# MoteinoR6USB.net
KiCad netlist of a schematic drawn in EAGLE
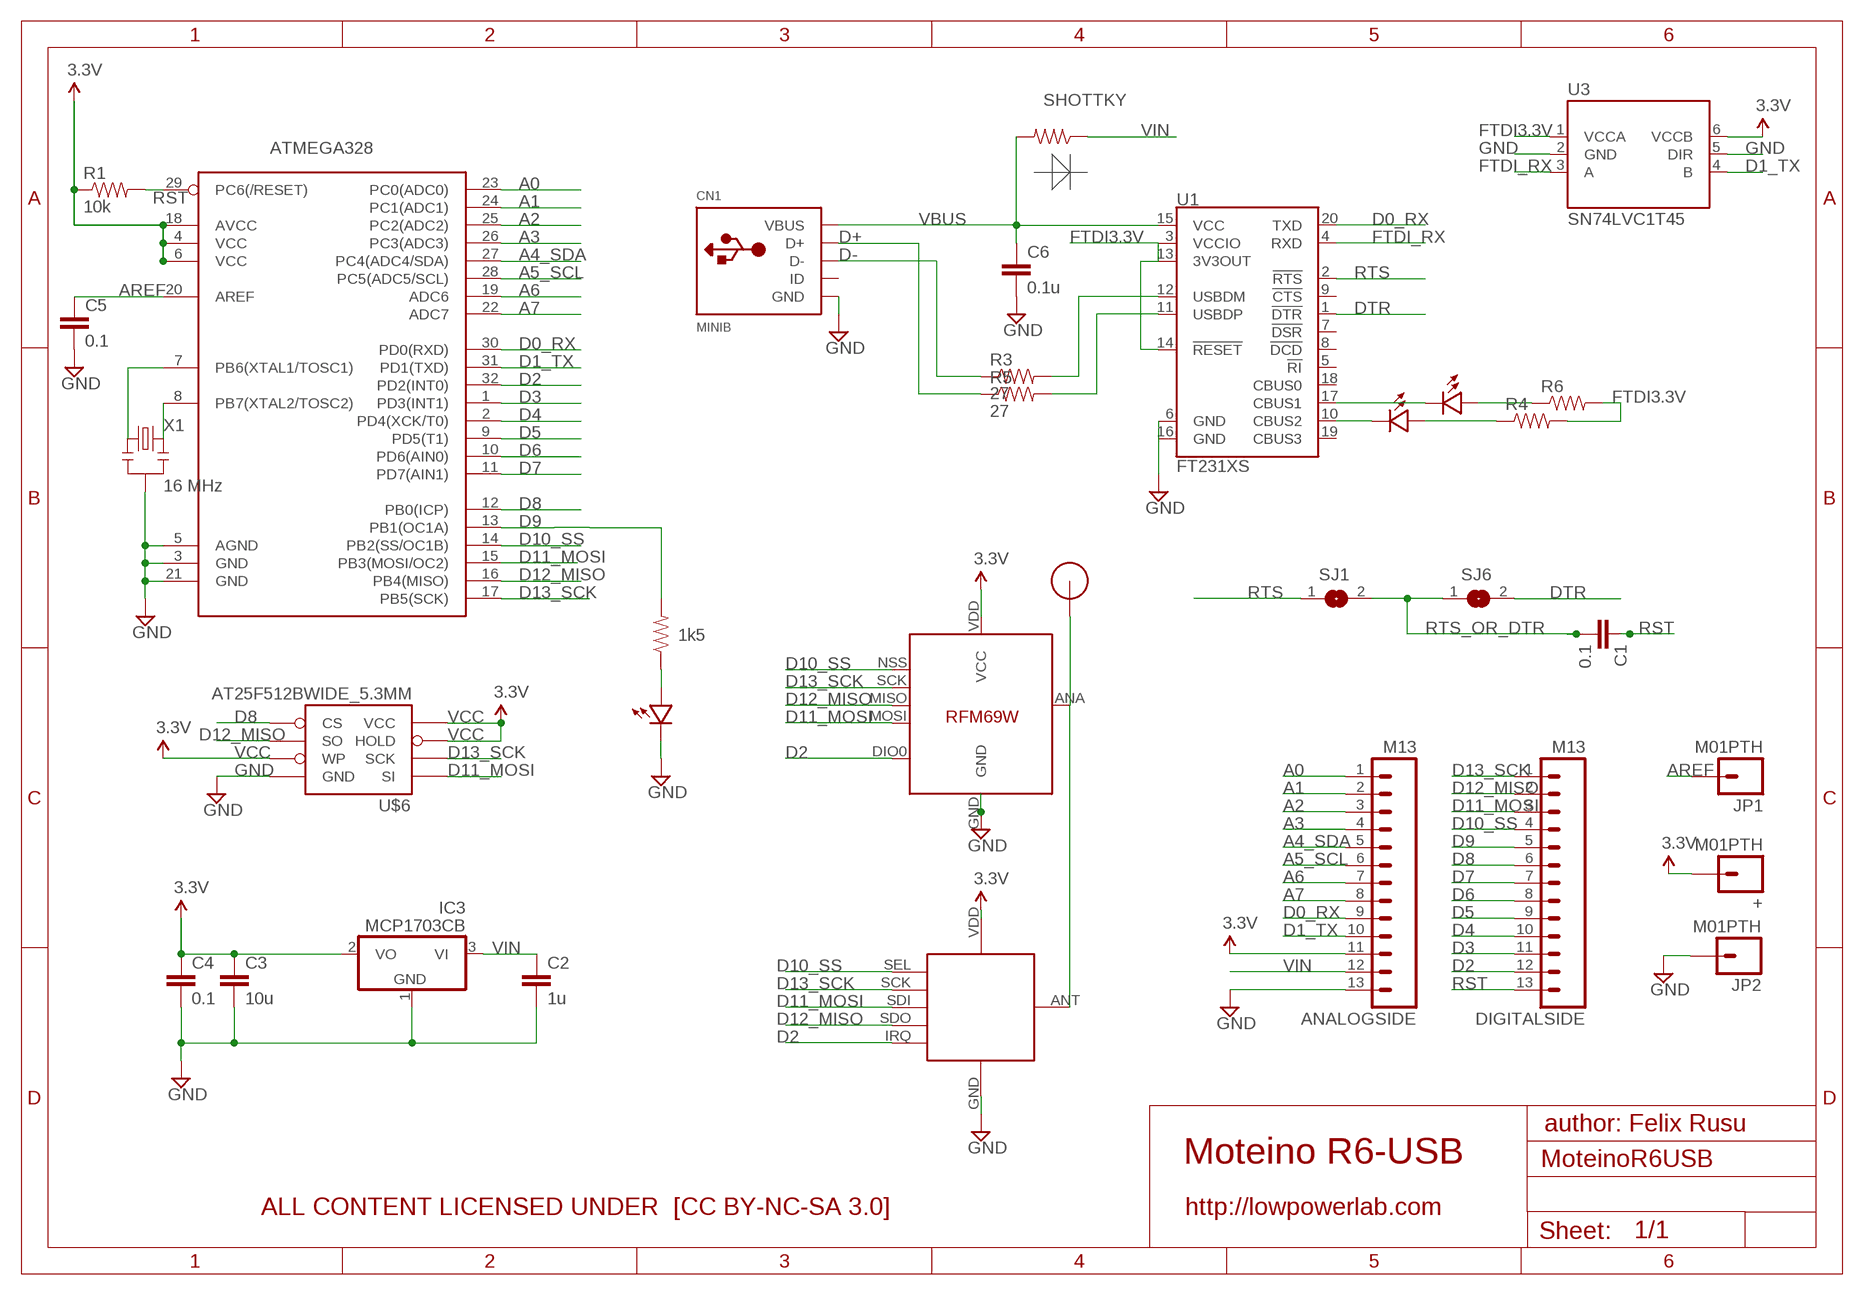
[diagram p0: schematic, sheet 1]

(export (version "E")
  (design (tool "Eeschema 10.0.6"))
  (components
    (comp (ref "+")
      (value "M01PTH")
      (footprint "eagle-import:1X01")
      (libsource (lib "eagle-import") (part "M01PTH"))
    )
    (comp (ref "ANALOGSIDE")
      (value "M13")
      (footprint "eagle-import:1X13")
      (libsource (lib "eagle-import") (part "M13"))
    )
    (comp (ref "ATMEGA328")
      (value "ATMega-328")
      (footprint "eagle-import:TQFP32-08")
      (libsource (lib "eagle-import") (part "ATMEGA168/328TQFP32"))
    )
    (comp (ref "C1")
      (value "0.1")
      (footprint "eagle-import:0603-CAP")
      (libsource (lib "eagle-import") (part "CAP0603-CAP"))
    )
    (comp (ref "C2")
      (value "1u")
      (footprint "eagle-import:0603-CAP")
      (libsource (lib "eagle-import") (part "CAP0603-CAP"))
    )
    (comp (ref "C3")
      (value "10u")
      (footprint "eagle-import:0805-CAP")
      (libsource (lib "eagle-import") (part "CAP0805-CAP"))
    )
    (comp (ref "C4")
      (value "0.1")
      (footprint "eagle-import:0603-CAP")
      (libsource (lib "eagle-import") (part "CAP0603-CAP"))
    )
    (comp (ref "C5")
      (value "0.1")
      (footprint "eagle-import:0603-CAP")
      (libsource (lib "eagle-import") (part "CAP0603-CAP"))
    )
    (comp (ref "C6")
      (value "0.1u")
      (footprint "eagle-import:0603-CAP")
      (libsource (lib "eagle-import") (part "CAP0603-CAP"))
    )
    (comp (ref "CN1")
      (value "MINIB")
      (footprint "eagle-import:USB-MINIB")
      (libsource (lib "eagle-import") (part "USBMINIB"))
    )
    (comp (ref "D")
      (value "SHOTTKY")
      (footprint "eagle-import:0603-RES")
      (libsource (lib "eagle-import") (part "RESISTOR0603-RES"))
    )
    (comp (ref "DIGITALSIDE")
      (value "M13")
      (footprint "eagle-import:1X13")
      (libsource (lib "eagle-import") (part "M13"))
    )
    (comp (ref "IC3")
      (value "MCP1703CB")
      (footprint "eagle-import:SOT23")
      (libsource (lib "eagle-import") (part "MCP1703CB"))
    )
    (comp (ref "JP1")
      (value "M01PTH")
      (footprint "eagle-import:1X01")
      (libsource (lib "eagle-import") (part "M01PTH"))
    )
    (comp (ref "JP2")
      (value "M01PTH")
      (footprint "eagle-import:1X01")
      (libsource (lib "eagle-import") (part "M01PTH"))
    )
    (comp (ref "R1")
      (value "10k")
      (footprint "eagle-import:0603-RES")
      (libsource (lib "eagle-import") (part "RESISTOR0603-RES"))
    )
    (comp (ref "R2")
      (value "1k5")
      (footprint "eagle-import:0603-RES")
      (libsource (lib "eagle-import") (part "RESISTOR0603-RES"))
    )
    (comp (ref "R3")
      (value "27")
      (footprint "eagle-import:0603-RES")
      (libsource (lib "eagle-import") (part "RESISTOR0603-RES"))
    )
    (comp (ref "R4")
      (value "RESISTOR0603-RES")
      (footprint "eagle-import:0603-RES")
      (libsource (lib "eagle-import") (part "RESISTOR0603-RES"))
    )
    (comp (ref "R5")
      (value "27")
      (footprint "eagle-import:0603-RES")
      (libsource (lib "eagle-import") (part "RESISTOR0603-RES"))
    )
    (comp (ref "R6")
      (value "RESISTOR0603-RES")
      (footprint "eagle-import:0603-RES")
      (libsource (lib "eagle-import") (part "RESISTOR0603-RES"))
    )
    (comp (ref "RFM12B")
      (value "RFM12B_MINPADS")
      (footprint "eagle-import:RFM12B-MINPADS")
      (libsource (lib "eagle-import") (part "RFM12B_MINPADS"))
    )
    (comp (ref "SJ1")
      (value "JUMPER")
      (footprint "eagle-import:SJW")
      (libsource (lib "eagle-import") (part "JUMPER"))
    )
    (comp (ref "SJ6")
      (value "JUMPER")
      (footprint "eagle-import:SJW")
      (libsource (lib "eagle-import") (part "JUMPER"))
    )
    (comp (ref "U$1")
      (value "RFM12B_ANTENNA")
      (footprint "eagle-import:RFM12B-ANTENNA")
      (libsource (lib "eagle-import") (part "RFM12B_ANTENNA"))
    )
    (comp (ref "U$2")
      (value "LED0603")
      (footprint "eagle-import:0603-LED")
      (libsource (lib "eagle-import") (part "LED0603"))
    )
    (comp (ref "U$4")
      (value "LED0603")
      (footprint "eagle-import:0603-LED")
      (libsource (lib "eagle-import") (part "LED0603"))
    )
    (comp (ref "U$5")
      (value "RFM69")
      (footprint "eagle-import:RFM69W-MINPADS")
      (libsource (lib "eagle-import") (part "RFM69"))
    )
    (comp (ref "U$6")
      (value "AT25F512BWIDE_5.3MM")
      (footprint "eagle-import:SO08WIDE")
      (libsource (lib "eagle-import") (part "AT25F512BWIDE_5.3MM"))
    )
    (comp (ref "U$7")
      (value "LED0603")
      (footprint "eagle-import:0603-LED")
      (libsource (lib "eagle-import") (part "LED0603"))
    )
    (comp (ref "U1")
      (value "FT231XS")
      (footprint "eagle-import:SSOP20_L")
      (libsource (lib "eagle-import") (part "FT231XS"))
    )
    (comp (ref "U3")
      (value "SN74LVC1T45")
      (footprint "eagle-import:SOT23-6")
      (libsource (lib "eagle-import") (part "SN74LVC1T45SOT-23"))
    )
    (comp (ref "X1")
      (value "16 MHz")
      (footprint "eagle-import:RESONATOR-SMD")
      (libsource (lib "eagle-import") (part "RESONATORSMD"))
    )
  )
  (nets
    (net (code "1") (name "/A0") (class "Default")
      (node (ref "ANALOGSIDE") (pin "1") (pinfunction "1_1") (pintype "passive"))
      (node (ref "ATMEGA328") (pin "23") (pinfunction "PC0(ADC0)_23") (pintype "bidirectional"))
    )
    (net (code "2") (name "/A1") (class "Default")
      (node (ref "ANALOGSIDE") (pin "2") (pinfunction "2_2") (pintype "passive"))
      (node (ref "ATMEGA328") (pin "24") (pinfunction "PC1(ADC1)_24") (pintype "bidirectional"))
    )
    (net (code "3") (name "/A2") (class "Default")
      (node (ref "ANALOGSIDE") (pin "3") (pinfunction "3_3") (pintype "passive"))
      (node (ref "ATMEGA328") (pin "25") (pinfunction "PC2(ADC2)_25") (pintype "bidirectional"))
    )
    (net (code "4") (name "/A3") (class "Default")
      (node (ref "ANALOGSIDE") (pin "4") (pinfunction "4_4") (pintype "passive"))
      (node (ref "ATMEGA328") (pin "26") (pinfunction "PC3(ADC3)_26") (pintype "bidirectional"))
    )
    (net (code "5") (name "/A4_SDA") (class "Default")
      (node (ref "ANALOGSIDE") (pin "5") (pinfunction "5_5") (pintype "passive"))
      (node (ref "ATMEGA328") (pin "27") (pinfunction "PC4(ADC4/SDA)_27") (pintype "bidirectional"))
    )
    (net (code "6") (name "/A5_SCL") (class "Default")
      (node (ref "ANALOGSIDE") (pin "6") (pinfunction "6_6") (pintype "passive"))
      (node (ref "ATMEGA328") (pin "28") (pinfunction "PC5(ADC5/SCL)_28") (pintype "bidirectional"))
    )
    (net (code "7") (name "/A6") (class "Default")
      (node (ref "ANALOGSIDE") (pin "7") (pinfunction "7_7") (pintype "passive"))
      (node (ref "ATMEGA328") (pin "19") (pinfunction "ADC6_19") (pintype "bidirectional"))
    )
    (net (code "8") (name "/A7") (class "Default")
      (node (ref "ANALOGSIDE") (pin "8") (pinfunction "8_8") (pintype "passive"))
      (node (ref "ATMEGA328") (pin "22") (pinfunction "ADC7_22") (pintype "bidirectional"))
    )
    (net (code "9") (name "/AREF") (class "Default")
      (node (ref "ATMEGA328") (pin "20") (pinfunction "AREF_20") (pintype "bidirectional"))
      (node (ref "C5") (pin "1") (pinfunction "1_1") (pintype "passive"))
      (node (ref "JP1") (pin "1") (pinfunction "1_1") (pintype "passive"))
    )
    (net (code "10") (name "/D+") (class "Default")
      (node (ref "CN1") (pin "D+") (pinfunction "D+_D+") (pintype "bidirectional"))
      (node (ref "R5") (pin "1") (pinfunction "1_1") (pintype "passive"))
    )
    (net (code "11") (name "/D-") (class "Default")
      (node (ref "CN1") (pin "D-") (pinfunction "D-_D-") (pintype "bidirectional"))
      (node (ref "R3") (pin "1") (pinfunction "1_1") (pintype "passive"))
    )
    (net (code "12") (name "/D0_RX") (class "Default")
      (node (ref "ANALOGSIDE") (pin "9") (pinfunction "9_9") (pintype "passive"))
      (node (ref "ATMEGA328") (pin "30") (pinfunction "PD0(RXD)_30") (pintype "bidirectional"))
      (node (ref "U1") (pin "20") (pinfunction "TXD_20") (pintype "bidirectional"))
    )
    (net (code "13") (name "/D1_TX") (class "Default")
      (node (ref "ANALOGSIDE") (pin "10") (pinfunction "10_10") (pintype "passive"))
      (node (ref "ATMEGA328") (pin "31") (pinfunction "PD1(TXD)_31") (pintype "bidirectional"))
      (node (ref "U3") (pin "4") (pinfunction "B_4") (pintype "bidirectional"))
    )
    (net (code "14") (name "/D2") (class "Default")
      (node (ref "ATMEGA328") (pin "32") (pinfunction "PD2(INT0)_32") (pintype "bidirectional"))
      (node (ref "DIGITALSIDE") (pin "12") (pinfunction "12_12") (pintype "passive"))
      (node (ref "RFM12B") (pin "IRQ") (pinfunction "IRQ_IRQ") (pintype "bidirectional"))
      (node (ref "U$5") (pin "DIO0") (pinfunction "DIO0_DIO0") (pintype "open_collector"))
    )
    (net (code "15") (name "/D3") (class "Default")
      (node (ref "ATMEGA328") (pin "1") (pinfunction "PD3(INT1)_1") (pintype "bidirectional"))
      (node (ref "DIGITALSIDE") (pin "11") (pinfunction "11_11") (pintype "passive"))
    )
    (net (code "16") (name "/D4") (class "Default")
      (node (ref "ATMEGA328") (pin "2") (pinfunction "PD4(XCK/T0)_2") (pintype "bidirectional"))
      (node (ref "DIGITALSIDE") (pin "10") (pinfunction "10_10") (pintype "passive"))
    )
    (net (code "17") (name "/D5") (class "Default")
      (node (ref "ATMEGA328") (pin "9") (pinfunction "PD5(T1)_9") (pintype "bidirectional"))
      (node (ref "DIGITALSIDE") (pin "9") (pinfunction "9_9") (pintype "passive"))
    )
    (net (code "18") (name "/D6") (class "Default")
      (node (ref "ATMEGA328") (pin "10") (pinfunction "PD6(AIN0)_10") (pintype "bidirectional"))
      (node (ref "DIGITALSIDE") (pin "8") (pinfunction "8_8") (pintype "passive"))
    )
    (net (code "19") (name "/D7") (class "Default")
      (node (ref "ATMEGA328") (pin "11") (pinfunction "PD7(AIN1)_11") (pintype "bidirectional"))
      (node (ref "DIGITALSIDE") (pin "7") (pinfunction "7_7") (pintype "passive"))
    )
    (net (code "20") (name "/D8") (class "Default")
      (node (ref "ATMEGA328") (pin "12") (pinfunction "PB0(ICP)_12") (pintype "bidirectional"))
      (node (ref "DIGITALSIDE") (pin "6") (pinfunction "6_6") (pintype "passive"))
      (node (ref "U$6") (pin "1") (pinfunction "CS_1") (pintype "bidirectional"))
    )
    (net (code "21") (name "/D9") (class "Default")
      (node (ref "ATMEGA328") (pin "13") (pinfunction "PB1(OC1A)_13") (pintype "bidirectional"))
      (node (ref "DIGITALSIDE") (pin "5") (pinfunction "5_5") (pintype "passive"))
      (node (ref "R2") (pin "2") (pinfunction "2_2") (pintype "passive"))
    )
    (net (code "22") (name "/D10_SS") (class "Default")
      (node (ref "ATMEGA328") (pin "14") (pinfunction "PB2(SS/OC1B)_14") (pintype "bidirectional"))
      (node (ref "DIGITALSIDE") (pin "4") (pinfunction "4_4") (pintype "passive"))
      (node (ref "RFM12B") (pin "SEL") (pinfunction "SEL_SEL") (pintype "bidirectional"))
      (node (ref "U$5") (pin "NSS") (pinfunction "SEL_NSS") (pintype "input"))
    )
    (net (code "23") (name "/D11_MOSI") (class "Default")
      (node (ref "ATMEGA328") (pin "15") (pinfunction "PB3(MOSI/OC2)_15") (pintype "bidirectional"))
      (node (ref "DIGITALSIDE") (pin "3") (pinfunction "3_3") (pintype "passive"))
      (node (ref "RFM12B") (pin "SDI") (pinfunction "SDI/MOSI_SDI") (pintype "bidirectional"))
      (node (ref "U$5") (pin "MOSI") (pinfunction "MOSI_MOSI") (pintype "output"))
      (node (ref "U$6") (pin "5") (pinfunction "SI_5") (pintype "bidirectional"))
    )
    (net (code "24") (name "/D12_MISO") (class "Default")
      (node (ref "ATMEGA328") (pin "16") (pinfunction "PB4(MISO)_16") (pintype "bidirectional"))
      (node (ref "DIGITALSIDE") (pin "2") (pinfunction "2_2") (pintype "passive"))
      (node (ref "RFM12B") (pin "SDO") (pinfunction "SDO/MISO_SDO") (pintype "bidirectional"))
      (node (ref "U$5") (pin "MISO") (pinfunction "MISO_MISO") (pintype "input"))
      (node (ref "U$6") (pin "2") (pinfunction "SO_2") (pintype "bidirectional"))
    )
    (net (code "25") (name "/D13_SCK") (class "Default")
      (node (ref "ATMEGA328") (pin "17") (pinfunction "PB5(SCK)_17") (pintype "bidirectional"))
      (node (ref "DIGITALSIDE") (pin "1") (pinfunction "1_1") (pintype "passive"))
      (node (ref "RFM12B") (pin "SCK") (pinfunction "SCK_SCK") (pintype "bidirectional"))
      (node (ref "U$5") (pin "SCK") (pinfunction "SCK_SCK") (pintype "input"))
      (node (ref "U$6") (pin "6") (pinfunction "SCK_6") (pintype "bidirectional"))
    )
    (net (code "26") (name "/DTR") (class "Default")
      (node (ref "SJ6") (pin "2") (pinfunction "2_2") (pintype "passive"))
      (node (ref "U1") (pin "1") (pinfunction "~{DTR}_1") (pintype "bidirectional"))
    )
    (net (code "27") (name "/FTDI3.3V") (class "Default")
      (node (ref "R4") (pin "2") (pinfunction "2_2") (pintype "passive"))
      (node (ref "R6") (pin "2") (pinfunction "2_2") (pintype "passive"))
      (node (ref "U1") (pin "13") (pinfunction "3V3OUT_13") (pintype "bidirectional"))
      (node (ref "U1") (pin "14") (pinfunction "~{RESET}_14") (pintype "bidirectional"))
      (node (ref "U1") (pin "3") (pinfunction "VCCIO_3") (pintype "bidirectional"))
      (node (ref "U3") (pin "1") (pinfunction "VCCA_1") (pintype "bidirectional"))
    )
    (net (code "28") (name "/FTDI_RX") (class "Default")
      (node (ref "U1") (pin "4") (pinfunction "RXD_4") (pintype "bidirectional"))
      (node (ref "U3") (pin "3") (pinfunction "A_3") (pintype "bidirectional"))
    )
    (net (code "29") (name "/RST") (class "Default")
      (node (ref "ATMEGA328") (pin "29") (pinfunction "PC6(/RESET)_29") (pintype "bidirectional"))
      (node (ref "C1") (pin "1") (pinfunction "1_1") (pintype "passive"))
      (node (ref "DIGITALSIDE") (pin "13") (pinfunction "13_13") (pintype "passive"))
      (node (ref "R1") (pin "2") (pinfunction "2_2") (pintype "passive"))
    )
    (net (code "30") (name "/RTS") (class "Default")
      (node (ref "SJ1") (pin "1") (pinfunction "1_1") (pintype "passive"))
      (node (ref "U1") (pin "2") (pinfunction "~{RTS}_2") (pintype "bidirectional"))
    )
    (net (code "31") (name "/RTS_OR_DTR") (class "Default")
      (node (ref "C1") (pin "2") (pinfunction "2_2") (pintype "passive"))
      (node (ref "SJ1") (pin "2") (pinfunction "2_2") (pintype "passive"))
      (node (ref "SJ6") (pin "1") (pinfunction "1_1") (pintype "passive"))
    )
    (net (code "32") (name "/VBUS") (class "Default")
      (node (ref "C6") (pin "1") (pinfunction "1_1") (pintype "passive"))
      (node (ref "CN1") (pin "VBUS") (pinfunction "VBUS_VBUS") (pintype "power_in"))
      (node (ref "D") (pin "2") (pinfunction "2_2") (pintype "passive"))
      (node (ref "U1") (pin "15") (pinfunction "VCC_15") (pintype "bidirectional"))
    )
    (net (code "33") (name "/VIN") (class "Default")
      (node (ref "ANALOGSIDE") (pin "12") (pinfunction "12_12") (pintype "passive"))
      (node (ref "C2") (pin "1") (pinfunction "1_1") (pintype "passive"))
      (node (ref "D") (pin "1") (pinfunction "1_1") (pintype "passive"))
      (node (ref "IC3") (pin "3") (pinfunction "VI_3") (pintype "input"))
    )
    (net (code "34") (name "3.3V") (class "Default")
      (node (ref "+") (pin "1") (pinfunction "1_1") (pintype "passive"))
      (node (ref "ANALOGSIDE") (pin "11") (pinfunction "11_11") (pintype "passive"))
      (node (ref "ATMEGA328") (pin "18") (pinfunction "AVCC_18") (pintype "bidirectional"))
      (node (ref "ATMEGA328") (pin "4") (pinfunction "VCC_4") (pintype "bidirectional"))
      (node (ref "ATMEGA328") (pin "6") (pinfunction "VCC_6") (pintype "bidirectional"))
      (node (ref "C3") (pin "1") (pinfunction "1_1") (pintype "passive"))
      (node (ref "C4") (pin "1") (pinfunction "1_1") (pintype "passive"))
      (node (ref "IC3") (pin "2") (pinfunction "VO_2") (pintype "passive"))
      (node (ref "R1") (pin "1") (pinfunction "1_1") (pintype "passive"))
      (node (ref "RFM12B") (pin "VDD") (pinfunction "VDD_VDD") (pintype "bidirectional"))
      (node (ref "U$5") (pin "VDD") (pinfunction "VCC_VDD") (pintype "power_in"))
      (node (ref "U$6") (pin "3") (pinfunction "WP_3") (pintype "bidirectional"))
      (node (ref "U$6") (pin "7") (pinfunction "HOLD_7") (pintype "bidirectional"))
      (node (ref "U$6") (pin "8") (pinfunction "VCC_8") (pintype "bidirectional"))
      (node (ref "U3") (pin "6") (pinfunction "VCCB_6") (pintype "bidirectional"))
    )
    (net (code "35") (name "GND") (class "Default")
      (node (ref "ANALOGSIDE") (pin "13") (pinfunction "13_13") (pintype "passive"))
      (node (ref "ATMEGA328") (pin "21") (pinfunction "GND_21") (pintype "bidirectional"))
      (node (ref "ATMEGA328") (pin "3") (pinfunction "GND_3") (pintype "bidirectional"))
      (node (ref "ATMEGA328") (pin "5") (pinfunction "AGND_5") (pintype "bidirectional"))
      (node (ref "C2") (pin "2") (pinfunction "2_2") (pintype "passive"))
      (node (ref "C3") (pin "2") (pinfunction "2_2") (pintype "passive"))
      (node (ref "C4") (pin "2") (pinfunction "2_2") (pintype "passive"))
      (node (ref "C5") (pin "2") (pinfunction "2_2") (pintype "passive"))
      (node (ref "C6") (pin "2") (pinfunction "2_2") (pintype "passive"))
      (node (ref "CN1") (pin "GND") (pinfunction "GND_GND") (pintype "power_in"))
      (node (ref "IC3") (pin "1") (pinfunction "GND_1") (pintype "passive"))
      (node (ref "JP2") (pin "1") (pinfunction "1_1") (pintype "passive"))
      (node (ref "RFM12B") (pin "GND") (pinfunction "GND_GND") (pintype "bidirectional"))
      (node (ref "U$2") (pin "MINUS") (pinfunction "MINUS_MINUS") (pintype "passive"))
      (node (ref "U$5") (pin "GND") (pinfunction "GND_GND") (pintype "power_in"))
      (node (ref "U$6") (pin "4") (pinfunction "GND_4") (pintype "bidirectional"))
      (node (ref "U1") (pin "16") (pinfunction "GND_16") (pintype "bidirectional"))
      (node (ref "U1") (pin "6") (pinfunction "GND_6") (pintype "bidirectional"))
      (node (ref "U3") (pin "2") (pinfunction "GND_2") (pintype "bidirectional"))
      (node (ref "U3") (pin "5") (pinfunction "DIR_5") (pintype "bidirectional"))
      (node (ref "X1") (pin "2") (pinfunction "2_2") (pintype "passive"))
    )
    (net (code "36") (name "Net-(ATMEGA328-PB6(XTAL1{slash}TOSC1))") (class "Default")
      (node (ref "ATMEGA328") (pin "7") (pinfunction "PB6(XTAL1/TOSC1)_7") (pintype "bidirectional"))
      (node (ref "X1") (pin "1") (pinfunction "1_1") (pintype "passive"))
    )
    (net (code "37") (name "Net-(ATMEGA328-PB7(XTAL2{slash}TOSC2))") (class "Default")
      (node (ref "ATMEGA328") (pin "8") (pinfunction "PB7(XTAL2/TOSC2)_8") (pintype "bidirectional"))
      (node (ref "X1") (pin "3") (pinfunction "3_3") (pintype "passive"))
    )
    (net (code "38") (name "Net-(R2-Pad1)") (class "Default")
      (node (ref "R2") (pin "1") (pinfunction "1_1") (pintype "passive"))
      (node (ref "U$2") (pin "PLUS") (pinfunction "PLUS_PLUS") (pintype "passive"))
    )
    (net (code "39") (name "Net-(R4-Pad1)") (class "Default")
      (node (ref "R4") (pin "1") (pinfunction "1_1") (pintype "passive"))
      (node (ref "U$7") (pin "PLUS") (pinfunction "PLUS_PLUS") (pintype "passive"))
    )
    (net (code "40") (name "Net-(R6-Pad1)") (class "Default")
      (node (ref "R6") (pin "1") (pinfunction "1_1") (pintype "passive"))
      (node (ref "U$4") (pin "PLUS") (pinfunction "PLUS_PLUS") (pintype "passive"))
    )
    (net (code "41") (name "Net-(U$1-1)") (class "Default")
      (node (ref "RFM12B") (pin "ANT") (pinfunction "ANT_ANT") (pintype "bidirectional"))
      (node (ref "U$1") (pin "P$1") (pinfunction "1_P$1") (pintype "bidirectional"))
      (node (ref "U$5") (pin "ANA") (pinfunction "ANT_ANA") (pintype "passive"))
    )
    (net (code "42") (name "Net-(U1-CBUS1)") (class "Default")
      (node (ref "U$4") (pin "MINUS") (pinfunction "MINUS_MINUS") (pintype "passive"))
      (node (ref "U1") (pin "17") (pinfunction "CBUS1_17") (pintype "bidirectional"))
    )
    (net (code "43") (name "Net-(U1-CBUS2)") (class "Default")
      (node (ref "U$7") (pin "MINUS") (pinfunction "MINUS_MINUS") (pintype "passive"))
      (node (ref "U1") (pin "10") (pinfunction "CBUS2_10") (pintype "bidirectional"))
    )
    (net (code "44") (name "Net-(U1-USBDM)") (class "Default")
      (node (ref "R3") (pin "2") (pinfunction "2_2") (pintype "passive"))
      (node (ref "U1") (pin "12") (pinfunction "USBDM_12") (pintype "bidirectional"))
    )
    (net (code "45") (name "Net-(U1-USBDP)") (class "Default")
      (node (ref "R5") (pin "2") (pinfunction "2_2") (pintype "passive"))
      (node (ref "U1") (pin "11") (pinfunction "USBDP_11") (pintype "bidirectional"))
    )
    (net (code "46") (name "unconnected-(CN1-PadID)") (class "Default")
      (node (ref "CN1") (pin "ID") (pinfunction "ID_ID") (pintype "bidirectional"))
    )
    (net (code "47") (name "unconnected-(U1-CBUS0-Pad18)") (class "Default")
      (node (ref "U1") (pin "18") (pinfunction "CBUS0_18") (pintype "bidirectional"))
    )
    (net (code "48") (name "unconnected-(U1-CBUS3-Pad19)") (class "Default")
      (node (ref "U1") (pin "19") (pinfunction "CBUS3_19") (pintype "bidirectional"))
    )
    (net (code "49") (name "unconnected-(U1-~{CTS}-Pad9)") (class "Default")
      (node (ref "U1") (pin "9") (pinfunction "~{CTS}_9") (pintype "bidirectional"))
    )
    (net (code "50") (name "unconnected-(U1-~{DCD}-Pad8)") (class "Default")
      (node (ref "U1") (pin "8") (pinfunction "~{DCD}_8") (pintype "bidirectional"))
    )
    (net (code "51") (name "unconnected-(U1-~{DSR}-Pad7)") (class "Default")
      (node (ref "U1") (pin "7") (pinfunction "~{DSR}_7") (pintype "bidirectional"))
    )
    (net (code "52") (name "unconnected-(U1-~{RI}-Pad5)") (class "Default")
      (node (ref "U1") (pin "5") (pinfunction "~{RI}_5") (pintype "bidirectional"))
    )
  )
)
